# VehicleSchematic.net
KiCad netlist of a schematic drawn in EAGLE
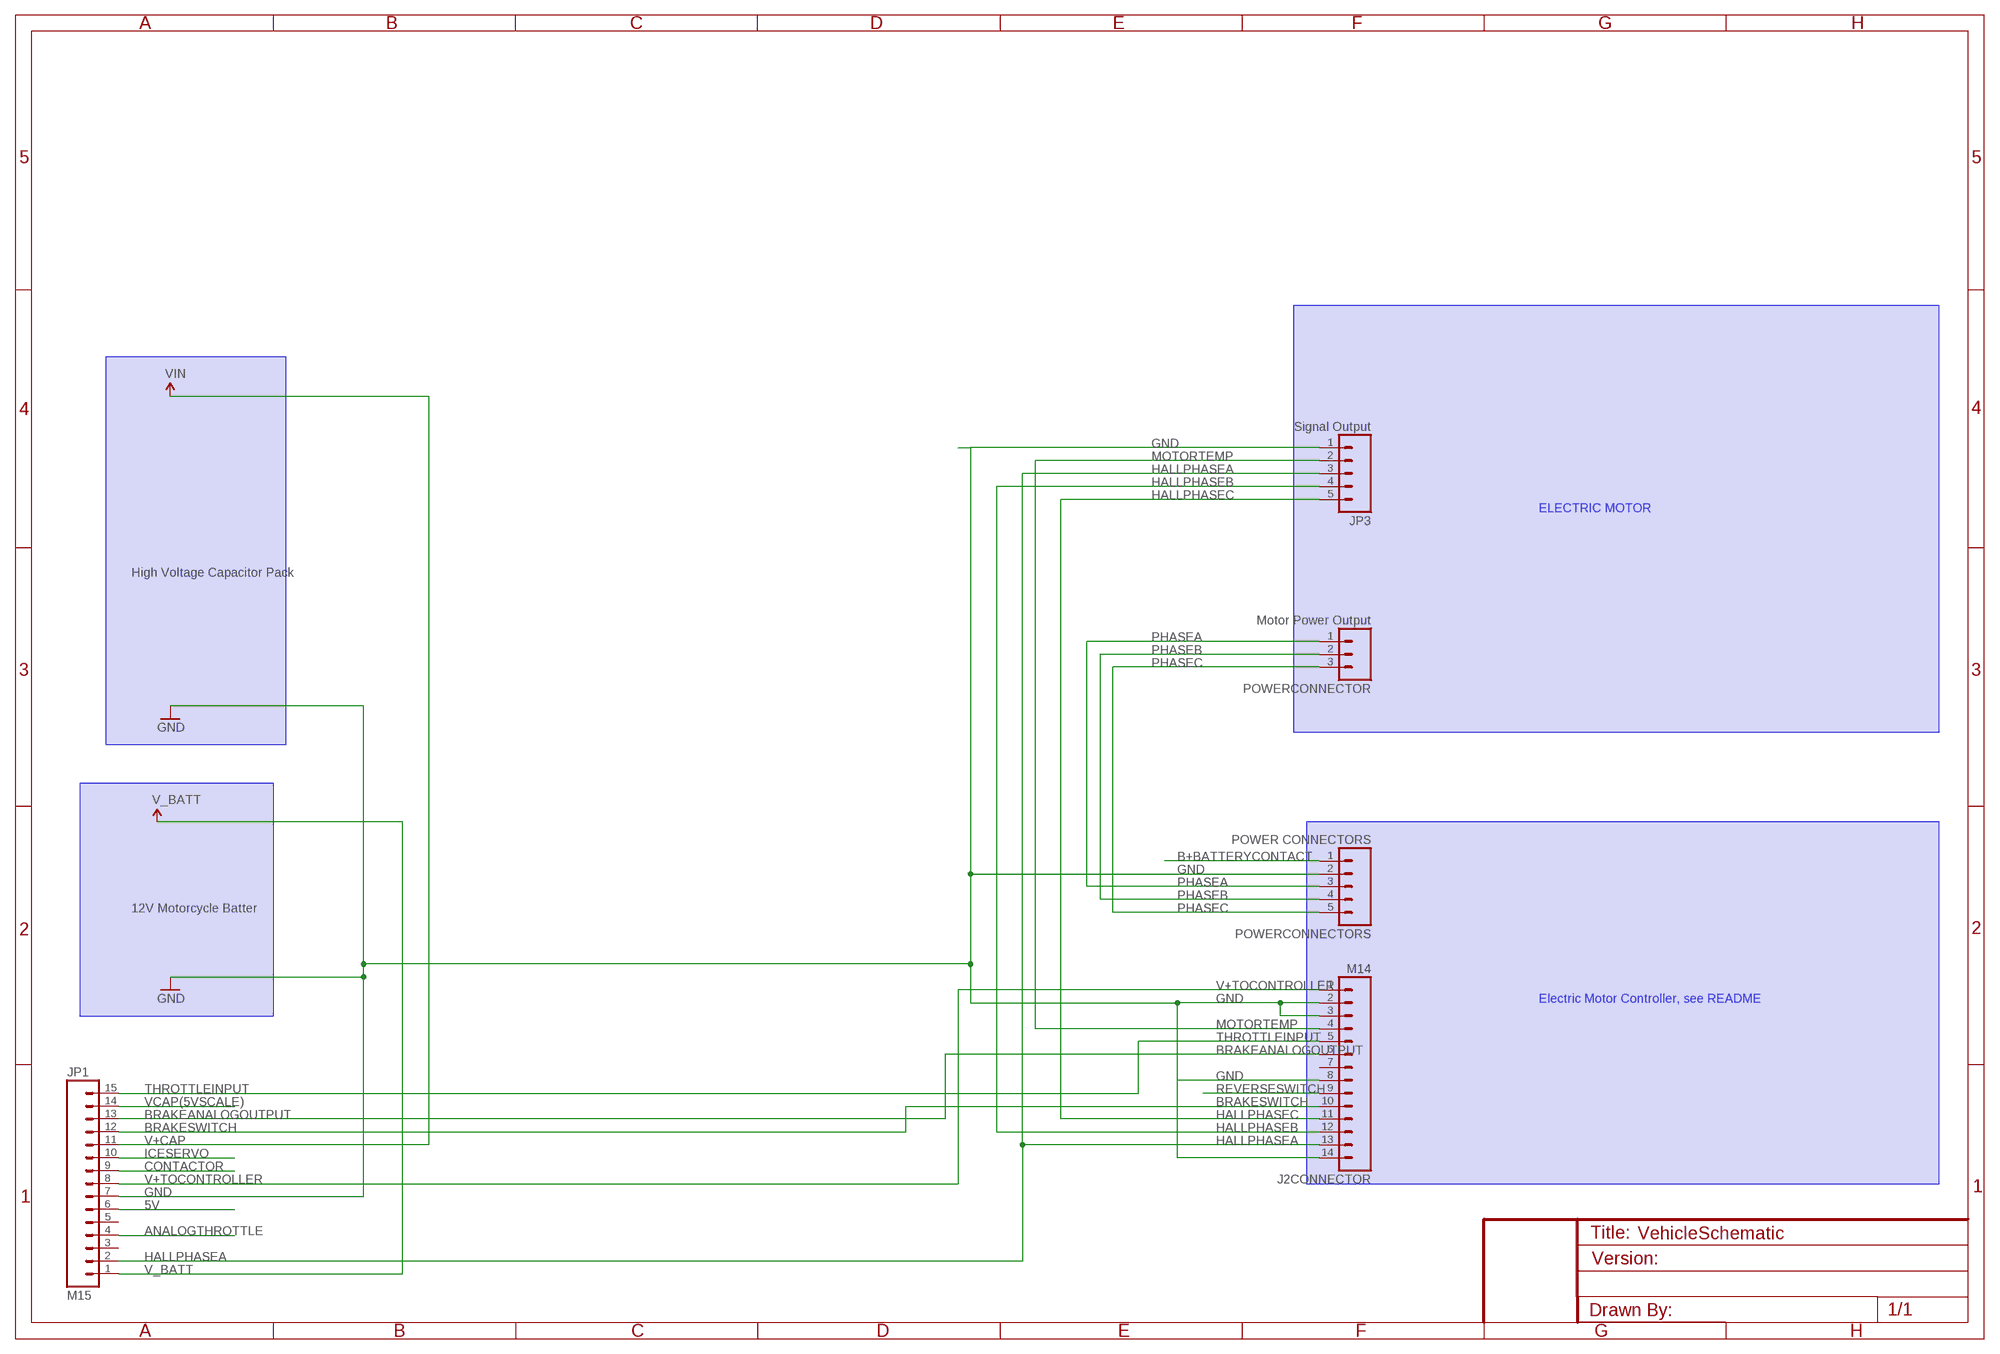
[diagram p0: schematic, sheet 1]

(export (version "E")
  (design (tool "Eeschema 10.0.6"))
  (components
    (comp (ref "J2CONNECTOR")
      (value "M14")
      (footprint "eagle-import:1X14")
      (libsource (lib "eagle-import") (part "M14"))
    )
    (comp (ref "JP1")
      (value "M15")
      (footprint "eagle-import:1X15")
      (libsource (lib "eagle-import") (part "M15"))
    )
    (comp (ref "JP3")
      (value "Signal Output")
      (footprint "eagle-import:1X05_NO_SILK")
      (libsource (lib "eagle-import") (part "M05NO_SILK"))
    )
    (comp (ref "POWERCONNECTOR")
      (value "Motor Power Output")
      (footprint "eagle-import:1X03_LONGPADS")
      (libsource (lib "eagle-import") (part "M03LONGPADS"))
    )
    (comp (ref "POWERCONNECTORS")
      (value "POWER CONNECTORS")
      (footprint "eagle-import:1X05_LOCK")
      (libsource (lib "eagle-import") (part "M05LOCK"))
    )
  )
  (nets
    (net (code "1") (name "/5V") (class "Default")
      (node (ref "JP1") (pin "6") (pinfunction "6_6") (pintype "passive"))
    )
    (net (code "2") (name "/ANALOGTHROTTLE") (class "Default")
      (node (ref "JP1") (pin "4") (pinfunction "4_4") (pintype "passive"))
    )
    (net (code "3") (name "/B+BATTERYCONTACT") (class "Default")
      (node (ref "POWERCONNECTORS") (pin "1") (pinfunction "1_1") (pintype "passive"))
    )
    (net (code "4") (name "/BRAKEANALOGOUTPUT") (class "Default")
      (node (ref "J2CONNECTOR") (pin "6") (pinfunction "6_6") (pintype "passive"))
      (node (ref "JP1") (pin "13") (pinfunction "13_13") (pintype "passive"))
    )
    (net (code "5") (name "/BRAKESWITCH") (class "Default")
      (node (ref "J2CONNECTOR") (pin "10") (pinfunction "10_10") (pintype "passive"))
      (node (ref "JP1") (pin "12") (pinfunction "12_12") (pintype "passive"))
    )
    (net (code "6") (name "/CONTACTOR") (class "Default")
      (node (ref "JP1") (pin "9") (pinfunction "9_9") (pintype "passive"))
    )
    (net (code "7") (name "/HALLPHASEA") (class "Default")
      (node (ref "J2CONNECTOR") (pin "13") (pinfunction "13_13") (pintype "passive"))
      (node (ref "JP1") (pin "2") (pinfunction "2_2") (pintype "passive"))
      (node (ref "JP3") (pin "3") (pinfunction "3_3") (pintype "passive"))
    )
    (net (code "8") (name "/HALLPHASEB") (class "Default")
      (node (ref "J2CONNECTOR") (pin "12") (pinfunction "12_12") (pintype "passive"))
      (node (ref "JP3") (pin "4") (pinfunction "4_4") (pintype "passive"))
    )
    (net (code "9") (name "/HALLPHASEC") (class "Default")
      (node (ref "J2CONNECTOR") (pin "11") (pinfunction "11_11") (pintype "passive"))
      (node (ref "JP3") (pin "5") (pinfunction "5_5") (pintype "passive"))
    )
    (net (code "10") (name "/ICESERVO") (class "Default")
      (node (ref "JP1") (pin "10") (pinfunction "10_10") (pintype "passive"))
    )
    (net (code "11") (name "/MOTORTEMP") (class "Default")
      (node (ref "J2CONNECTOR") (pin "4") (pinfunction "4_4") (pintype "passive"))
      (node (ref "JP3") (pin "2") (pinfunction "2_2") (pintype "passive"))
    )
    (net (code "12") (name "/PHASEA") (class "Default")
      (node (ref "POWERCONNECTOR") (pin "1") (pinfunction "1_1") (pintype "passive"))
      (node (ref "POWERCONNECTORS") (pin "3") (pinfunction "3_3") (pintype "passive"))
    )
    (net (code "13") (name "/PHASEB") (class "Default")
      (node (ref "POWERCONNECTOR") (pin "2") (pinfunction "2_2") (pintype "passive"))
      (node (ref "POWERCONNECTORS") (pin "4") (pinfunction "4_4") (pintype "passive"))
    )
    (net (code "14") (name "/PHASEC") (class "Default")
      (node (ref "POWERCONNECTOR") (pin "3") (pinfunction "3_3") (pintype "passive"))
      (node (ref "POWERCONNECTORS") (pin "5") (pinfunction "5_5") (pintype "passive"))
    )
    (net (code "15") (name "/REVERSESWITCH") (class "Default")
      (node (ref "J2CONNECTOR") (pin "9") (pinfunction "9_9") (pintype "passive"))
    )
    (net (code "16") (name "/THROTTLEINPUT") (class "Default")
      (node (ref "J2CONNECTOR") (pin "5") (pinfunction "5_5") (pintype "passive"))
      (node (ref "JP1") (pin "15") (pinfunction "15_15") (pintype "passive"))
    )
    (net (code "17") (name "/V+TOCONTROLLER") (class "Default")
      (node (ref "J2CONNECTOR") (pin "1") (pinfunction "1_1") (pintype "passive"))
      (node (ref "JP1") (pin "8") (pinfunction "8_8") (pintype "passive"))
    )
    (net (code "18") (name "/VCAP(5VSCALE)") (class "Default")
      (node (ref "JP1") (pin "14") (pinfunction "14_14") (pintype "passive"))
    )
    (net (code "19") (name "GND") (class "Default")
      (node (ref "J2CONNECTOR") (pin "14") (pinfunction "14_14") (pintype "passive"))
      (node (ref "J2CONNECTOR") (pin "2") (pinfunction "2_2") (pintype "passive"))
      (node (ref "J2CONNECTOR") (pin "3") (pinfunction "3_3") (pintype "passive"))
      (node (ref "J2CONNECTOR") (pin "8") (pinfunction "8_8") (pintype "passive"))
      (node (ref "JP1") (pin "7") (pinfunction "7_7") (pintype "passive"))
      (node (ref "JP3") (pin "1") (pinfunction "1_1") (pintype "passive"))
      (node (ref "POWERCONNECTORS") (pin "2") (pinfunction "2_2") (pintype "passive"))
    )
    (net (code "20") (name "VIN") (class "Default")
      (node (ref "JP1") (pin "11") (pinfunction "11_11") (pintype "passive"))
    )
    (net (code "21") (name "V_BATT") (class "Default")
      (node (ref "JP1") (pin "1") (pinfunction "1_1") (pintype "passive"))
    )
    (net (code "22") (name "unconnected-(J2CONNECTOR-Pad7)") (class "Default")
      (node (ref "J2CONNECTOR") (pin "7") (pinfunction "7_7") (pintype "passive"))
    )
    (net (code "23") (name "unconnected-(JP1-Pad3)") (class "Default")
      (node (ref "JP1") (pin "3") (pinfunction "3_3") (pintype "passive"))
    )
    (net (code "24") (name "unconnected-(JP1-Pad5)") (class "Default")
      (node (ref "JP1") (pin "5") (pinfunction "5_5") (pintype "passive"))
    )
  )
)
